# ain.net
KiCad netlist of a schematic drawn in EAGLE
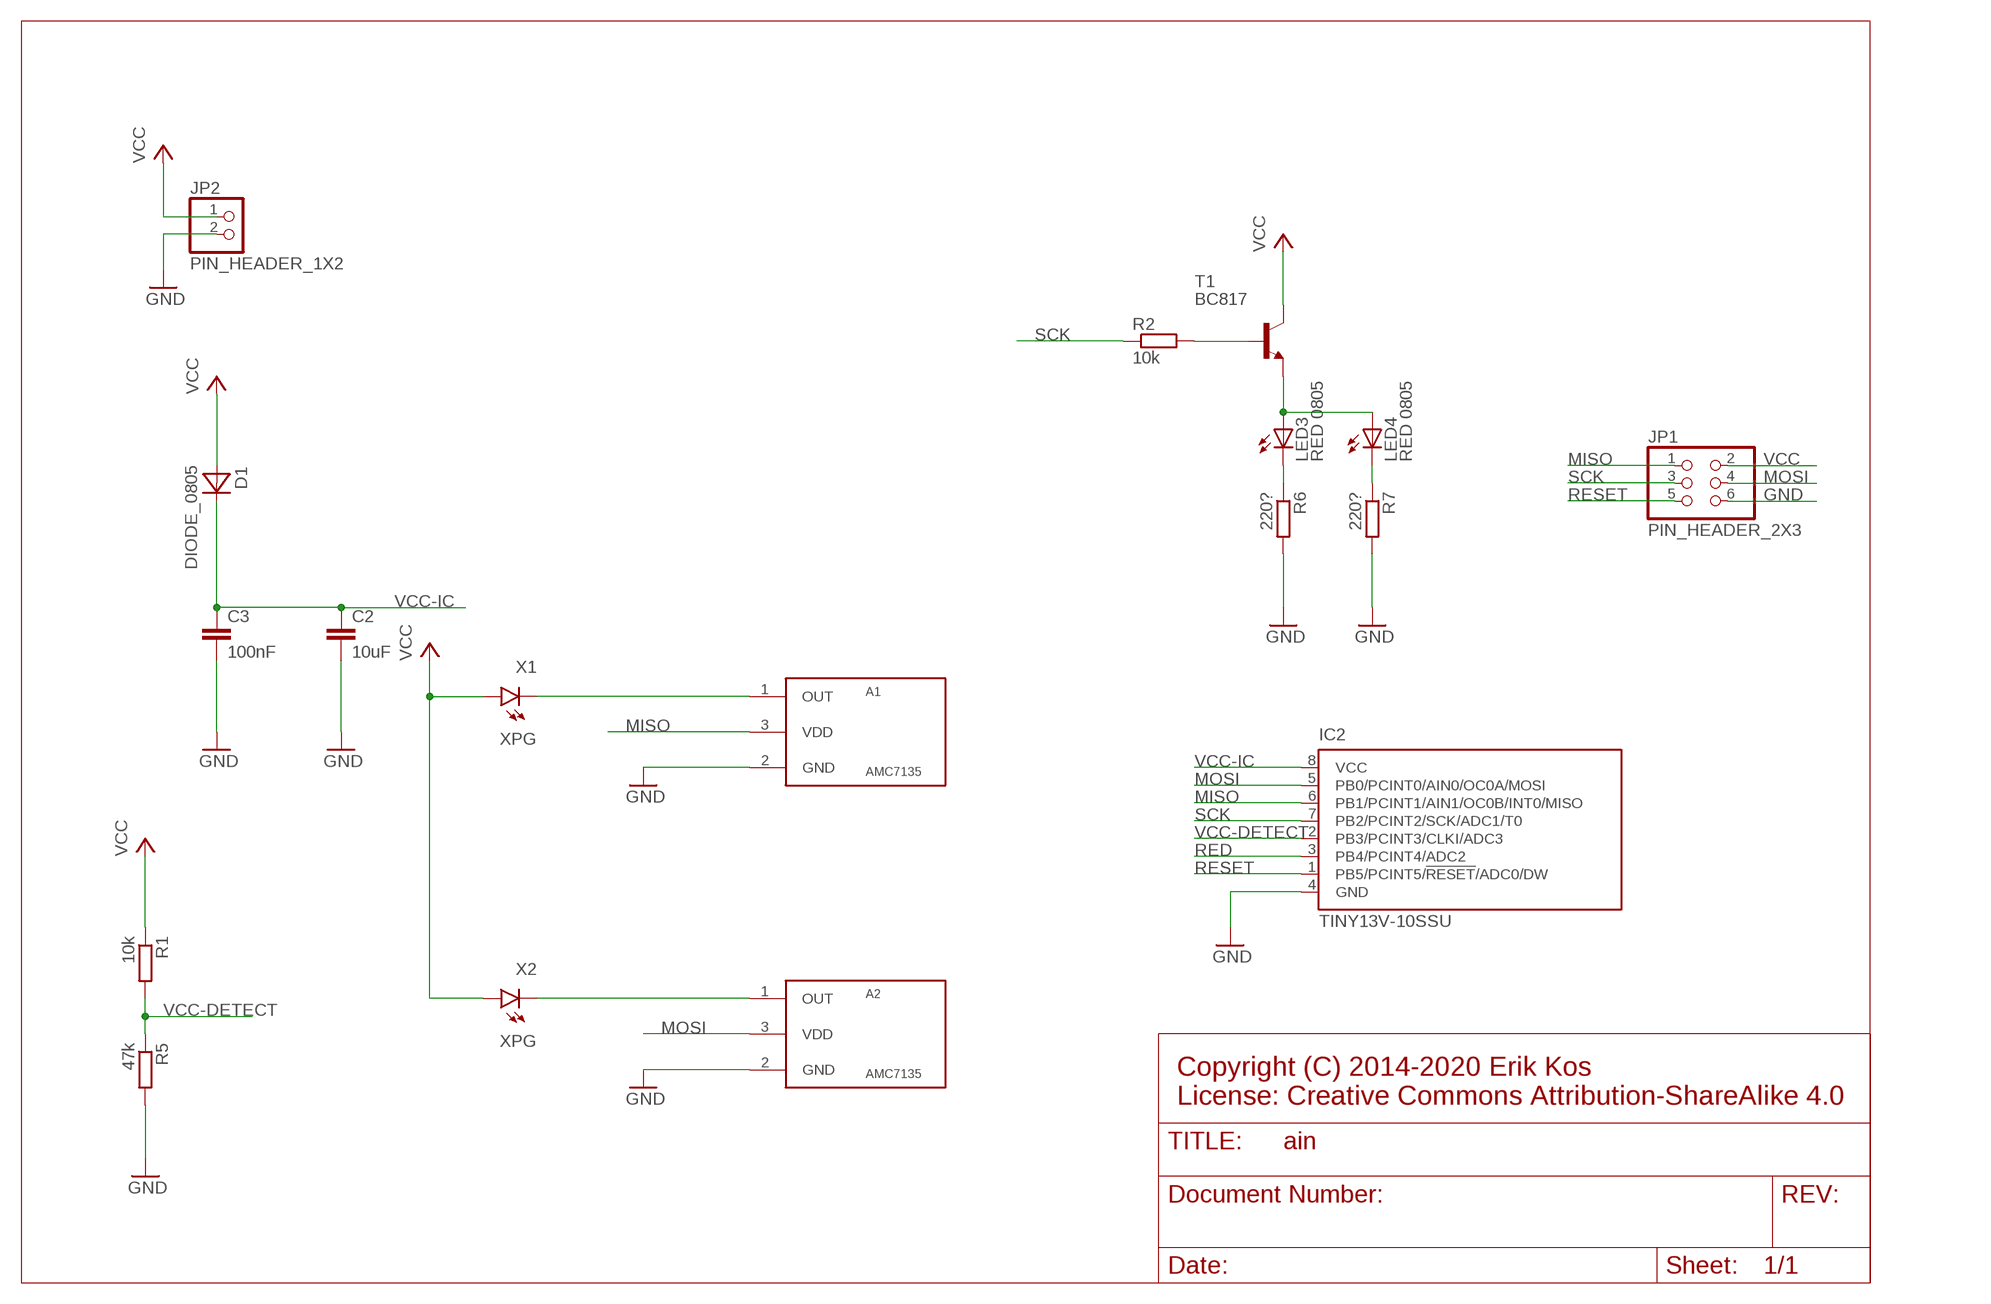
[diagram p0: schematic, sheet 1]

(export (version "E")
  (design (tool "Eeschema 10.0.6"))
  (components
    (comp (ref "A1")
      (value "AMC7135")
      (footprint "eagle-import:SOT-89")
      (libsource (lib "eagle-import") (part "AMC7135"))
    )
    (comp (ref "A2")
      (value "AMC7135")
      (footprint "eagle-import:SOT-89")
      (libsource (lib "eagle-import") (part "AMC7135"))
    )
    (comp (ref "C2")
      (value "10uF")
      (footprint "eagle-import:C0805")
      (libsource (lib "eagle-import") (part "C-EUC0805"))
    )
    (comp (ref "C3")
      (value "100nF")
      (footprint "eagle-import:C0805")
      (libsource (lib "eagle-import") (part "C-EUC0805"))
    )
    (comp (ref "D1")
      (value "DIODE_0805")
      (footprint "eagle-import:0805")
      (libsource (lib "eagle-import") (part "DIODE_0805"))
    )
    (comp (ref "IC2")
      (value "TINY13V-10SSU")
      (footprint "eagle-import:8S1")
      (fields (field (name "MPN") "ATTINY13V-10SSU"))
      (libsource (lib "eagle-import") (part "TINY13SSUV-10"))
    )
    (comp (ref "JP1")
      (value "PIN_HEADER_2X3")
      (footprint "eagle-import:PIN_HEADER_2X3")
      (libsource (lib "eagle-import") (part "PIN_HEADER_2X3"))
    )
    (comp (ref "JP2")
      (value "PIN_HEADER_1X2")
      (footprint "eagle-import:PIN_HEADER_1X2")
      (libsource (lib "eagle-import") (part "PIN_HEADER_1X2"))
    )
    (comp (ref "LED3")
      (value "RED 0805")
      (footprint "eagle-import:SML0805")
      (libsource (lib "eagle-import") (part "LEDSML0805"))
    )
    (comp (ref "LED4")
      (value "RED 0805")
      (footprint "eagle-import:SML0805")
      (libsource (lib "eagle-import") (part "LEDSML0805"))
    )
    (comp (ref "R1")
      (value "10k")
      (footprint "eagle-import:M0805")
      (libsource (lib "eagle-import") (part "R-EU_M0805"))
    )
    (comp (ref "R2")
      (value "10k")
      (footprint "eagle-import:M0805")
      (libsource (lib "eagle-import") (part "R-EU_M0805"))
    )
    (comp (ref "R5")
      (value "47k")
      (footprint "eagle-import:M0805")
      (libsource (lib "eagle-import") (part "R-EU_M0805"))
    )
    (comp (ref "R6")
      (value "220?")
      (footprint "eagle-import:M0805")
      (libsource (lib "eagle-import") (part "R-EU_M0805"))
    )
    (comp (ref "R7")
      (value "220?")
      (footprint "eagle-import:M0805")
      (libsource (lib "eagle-import") (part "R-EU_M0805"))
    )
    (comp (ref "T1")
      (value "BC817")
      (footprint "eagle-import:SOT23-BEC")
      (libsource (lib "eagle-import") (part "-NPN-SOT23-BECBC817-25"))
    )
    (comp (ref "X1")
      (value "XPG")
      (footprint "eagle-import:XPG")
      (libsource (lib "eagle-import") (part "XPG"))
    )
    (comp (ref "X2")
      (value "XPG")
      (footprint "eagle-import:XPG")
      (libsource (lib "eagle-import") (part "XPG"))
    )
  )
  (nets
    (net (code "1") (name "/MISO") (class "Default")
      (node (ref "A1") (pin "3") (pinfunction "VDD_3") (pintype "bidirectional"))
      (node (ref "IC2") (pin "6") (pinfunction "PB1/PCINT1/AIN1/OC0B/INT0/MISO_6") (pintype "bidirectional"))
      (node (ref "JP1") (pin "1") (pinfunction "1_1") (pintype "passive"))
    )
    (net (code "2") (name "/MOSI") (class "Default")
      (node (ref "A2") (pin "3") (pinfunction "VDD_3") (pintype "bidirectional"))
      (node (ref "IC2") (pin "5") (pinfunction "PB0/PCINT0/AIN0/OC0A/MOSI_5") (pintype "bidirectional"))
      (node (ref "JP1") (pin "4") (pinfunction "4_4") (pintype "passive"))
    )
    (net (code "3") (name "/RED") (class "Default")
      (node (ref "IC2") (pin "3") (pinfunction "PB4/PCINT4/ADC2_3") (pintype "bidirectional"))
    )
    (net (code "4") (name "/RESET") (class "Default")
      (node (ref "IC2") (pin "1") (pinfunction "PB5/PCINT5/~{RESET}/ADC0/DW_1") (pintype "bidirectional"))
      (node (ref "JP1") (pin "5") (pinfunction "5_5") (pintype "passive"))
    )
    (net (code "5") (name "/SCK") (class "Default")
      (node (ref "IC2") (pin "7") (pinfunction "PB2/PCINT2/SCK/ADC1/T0_7") (pintype "bidirectional"))
      (node (ref "JP1") (pin "3") (pinfunction "3_3") (pintype "passive"))
      (node (ref "R2") (pin "1") (pinfunction "1_1") (pintype "passive"))
    )
    (net (code "6") (name "/VCC-DETECT") (class "Default")
      (node (ref "IC2") (pin "2") (pinfunction "PB3/PCINT3/CLKI/ADC3_2") (pintype "bidirectional"))
      (node (ref "R1") (pin "2") (pinfunction "2_2") (pintype "passive"))
      (node (ref "R5") (pin "1") (pinfunction "1_1") (pintype "passive"))
    )
    (net (code "7") (name "/VCC-IC") (class "Default")
      (node (ref "C2") (pin "1") (pinfunction "1_1") (pintype "passive"))
      (node (ref "C3") (pin "1") (pinfunction "1_1") (pintype "passive"))
      (node (ref "D1") (pin "2") (pinfunction "C_2") (pintype "passive"))
      (node (ref "IC2") (pin "8") (pinfunction "VCC_8") (pintype "power_in"))
    )
    (net (code "8") (name "GND") (class "Default")
      (node (ref "A1") (pin "2") (pinfunction "GND_2") (pintype "bidirectional"))
      (node (ref "A2") (pin "2") (pinfunction "GND_2") (pintype "bidirectional"))
      (node (ref "C2") (pin "2") (pinfunction "2_2") (pintype "passive"))
      (node (ref "C3") (pin "2") (pinfunction "2_2") (pintype "passive"))
      (node (ref "IC2") (pin "4") (pinfunction "GND_4") (pintype "power_in"))
      (node (ref "JP1") (pin "6") (pinfunction "6_6") (pintype "passive"))
      (node (ref "JP2") (pin "2") (pinfunction "2_2") (pintype "passive"))
      (node (ref "R5") (pin "2") (pinfunction "2_2") (pintype "passive"))
      (node (ref "R6") (pin "2") (pinfunction "2_2") (pintype "passive"))
      (node (ref "R7") (pin "2") (pinfunction "2_2") (pintype "passive"))
    )
    (net (code "9") (name "Net-(A1-OUT)") (class "Default")
      (node (ref "A1") (pin "1") (pinfunction "OUT_1") (pintype "bidirectional"))
      (node (ref "X1") (pin "2") (pinfunction "C_2") (pintype "passive"))
    )
    (net (code "10") (name "Net-(A2-OUT)") (class "Default")
      (node (ref "A2") (pin "1") (pinfunction "OUT_1") (pintype "bidirectional"))
      (node (ref "X2") (pin "2") (pinfunction "C_2") (pintype "passive"))
    )
    (net (code "11") (name "Net-(LED3-PadA)") (class "Default")
      (node (ref "LED3") (pin "A") (pinfunction "A_A") (pintype "passive"))
      (node (ref "LED4") (pin "A") (pinfunction "A_A") (pintype "passive"))
      (node (ref "T1") (pin "E") (pinfunction "E_E") (pintype "passive"))
    )
    (net (code "12") (name "Net-(LED3-PadC)") (class "Default")
      (node (ref "LED3") (pin "C") (pinfunction "C_C") (pintype "passive"))
      (node (ref "R6") (pin "1") (pinfunction "1_1") (pintype "passive"))
    )
    (net (code "13") (name "Net-(LED4-PadC)") (class "Default")
      (node (ref "LED4") (pin "C") (pinfunction "C_C") (pintype "passive"))
      (node (ref "R7") (pin "1") (pinfunction "1_1") (pintype "passive"))
    )
    (net (code "14") (name "Net-(R2-Pad2)") (class "Default")
      (node (ref "R2") (pin "2") (pinfunction "2_2") (pintype "passive"))
      (node (ref "T1") (pin "B") (pinfunction "B_B") (pintype "passive"))
    )
    (net (code "15") (name "VCC") (class "Default")
      (node (ref "D1") (pin "1") (pinfunction "A_1") (pintype "passive"))
      (node (ref "JP1") (pin "2") (pinfunction "2_2") (pintype "passive"))
      (node (ref "JP2") (pin "1") (pinfunction "1_1") (pintype "passive"))
      (node (ref "R1") (pin "1") (pinfunction "1_1") (pintype "passive"))
      (node (ref "T1") (pin "C") (pinfunction "C_C") (pintype "passive"))
      (node (ref "X1") (pin "1") (pinfunction "A_1") (pintype "passive"))
      (node (ref "X2") (pin "1") (pinfunction "A_1") (pintype "passive"))
    )
  )
)
